# atmega2560test.net
KiCad netlist of a schematic drawn in EAGLE
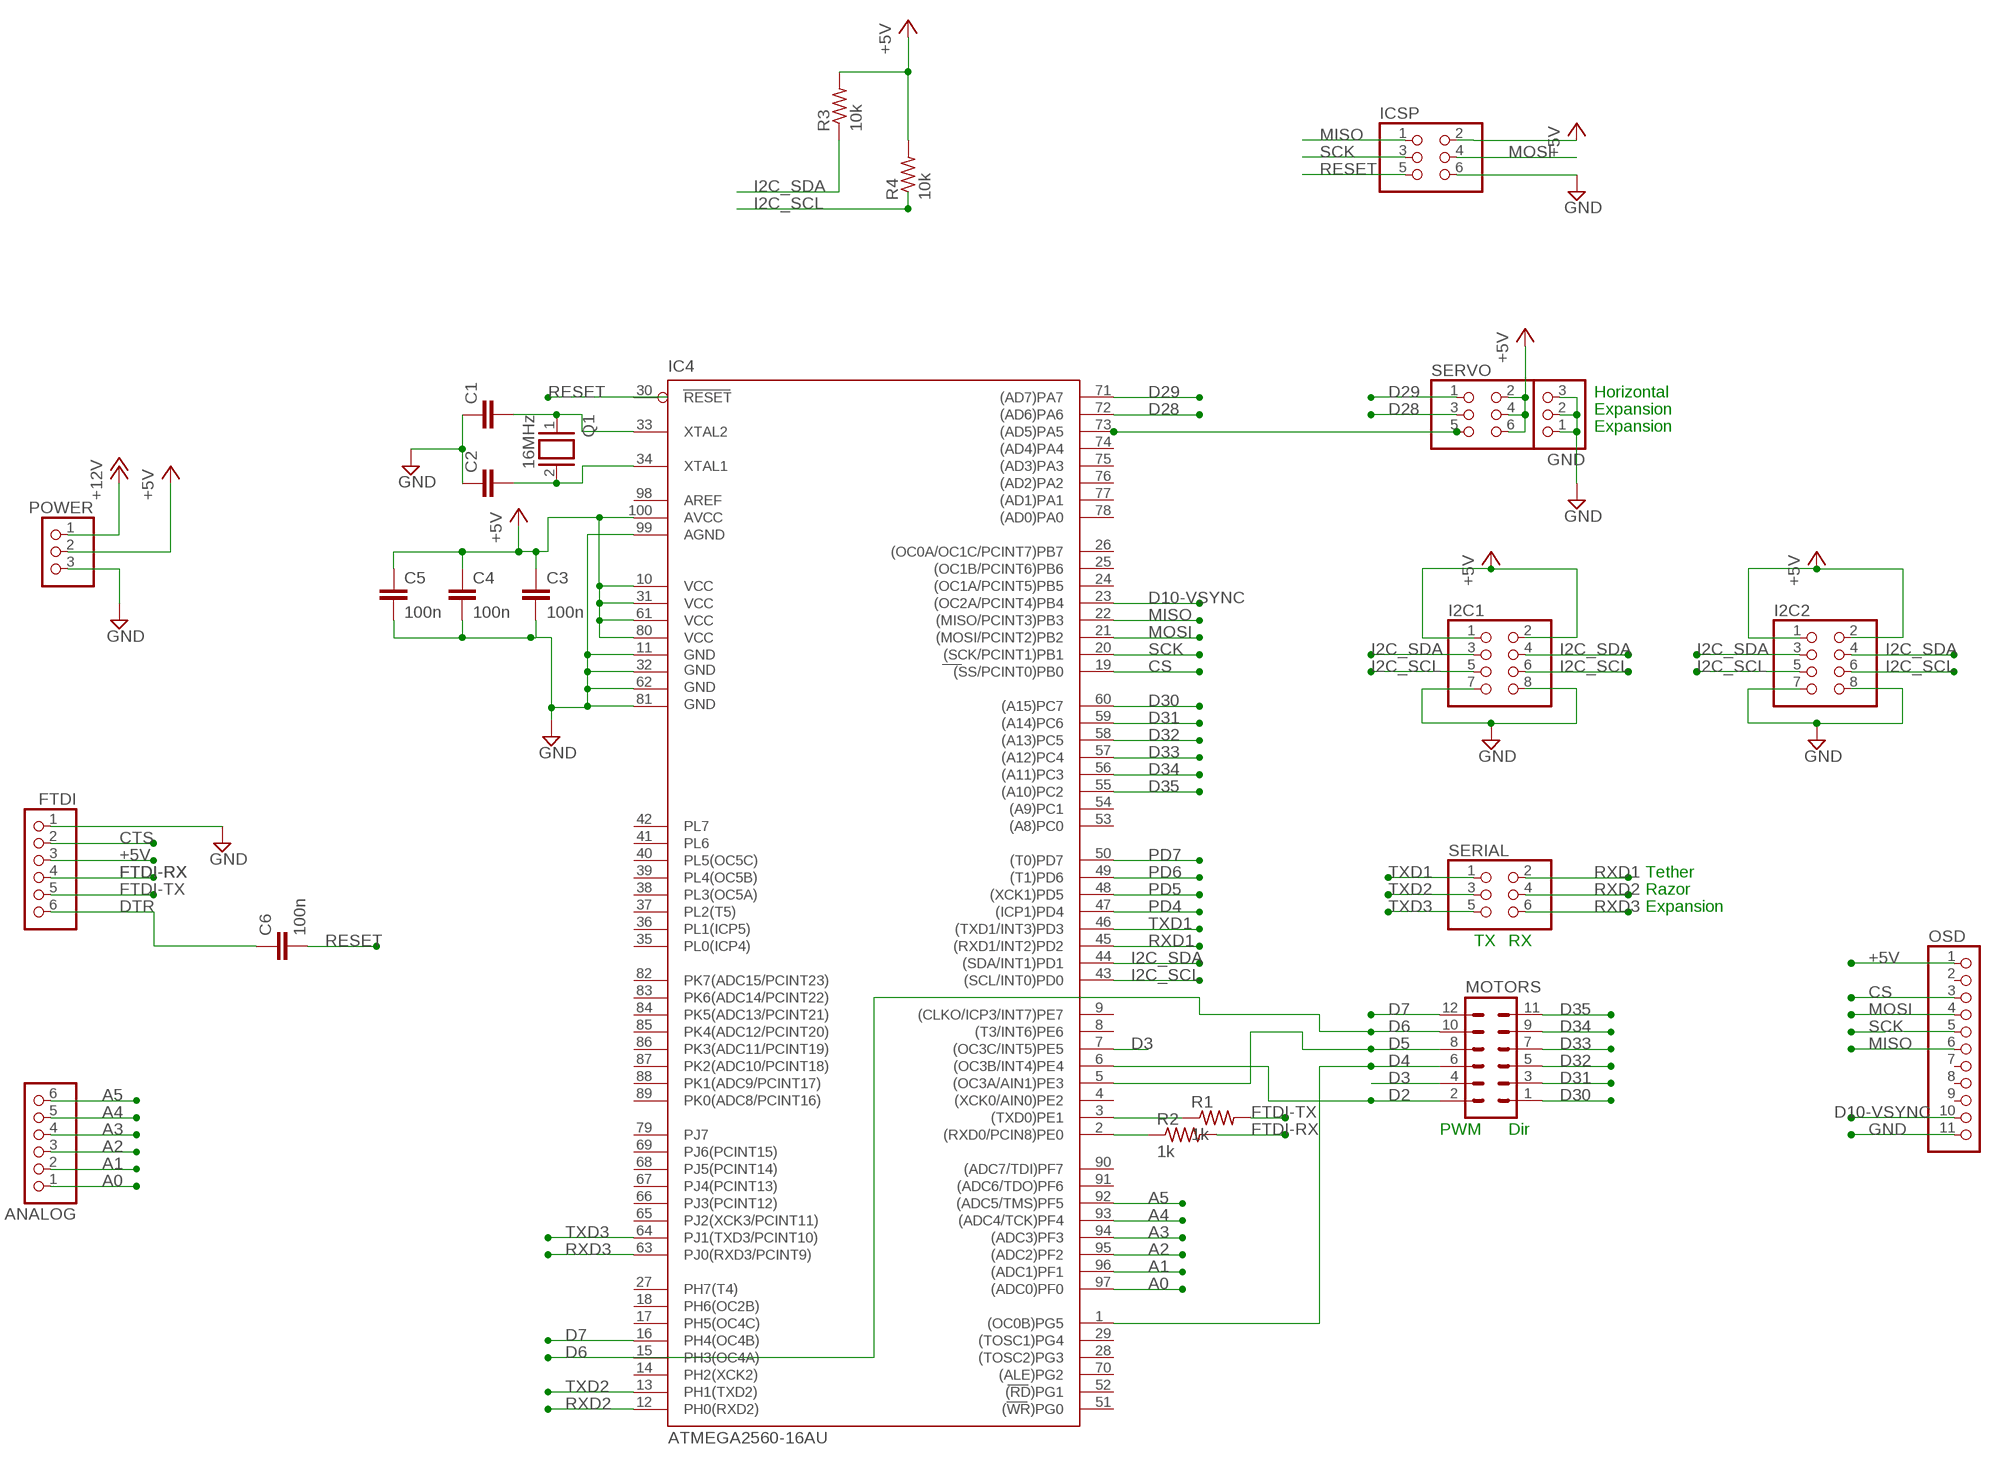
[diagram p0: schematic, sheet 1]

(export (version "E")
  (design (tool "Eeschema 10.0.6"))
  (components
    (comp (ref "ANALOG")
      (value "PINHD-1X6")
      (footprint "eagle-import:1X06")
      (libsource (lib "eagle-import") (part "PINHD-1X6"))
    )
    (comp (ref "C1")
      (value "C5/3.5")
      (footprint "eagle-import:C5B3.5")
      (libsource (lib "eagle-import") (part "C5/3.5"))
    )
    (comp (ref "C2")
      (value "C5/3.5")
      (footprint "eagle-import:C5B3.5")
      (libsource (lib "eagle-import") (part "C5/3.5"))
    )
    (comp (ref "C3")
      (value "100n")
      (footprint "eagle-import:C5B3.5")
      (libsource (lib "eagle-import") (part "C5/3.5"))
    )
    (comp (ref "C4")
      (value "100n")
      (footprint "eagle-import:C5B3.5")
      (libsource (lib "eagle-import") (part "C5/3.5"))
    )
    (comp (ref "C5")
      (value "100n")
      (footprint "eagle-import:C5B3.5")
      (libsource (lib "eagle-import") (part "C5/3.5"))
    )
    (comp (ref "C6")
      (value "100n")
      (footprint "eagle-import:C050-030X075")
      (libsource (lib "eagle-import") (part "C-EU050-030X075"))
    )
    (comp (ref "FTDI")
      (value "PINHD-1X6")
      (footprint "eagle-import:1X06")
      (libsource (lib "eagle-import") (part "PINHD-1X6"))
    )
    (comp (ref "GND")
      (value "PINHD-1X3")
      (footprint "eagle-import:1X03")
      (libsource (lib "eagle-import") (part "PINHD-1X3"))
    )
    (comp (ref "I2C1")
      (value "PINHD-2X4")
      (footprint "eagle-import:2X04")
      (libsource (lib "eagle-import") (part "PINHD-2X4"))
    )
    (comp (ref "I2C2")
      (value "PINHD-2X4")
      (footprint "eagle-import:2X04")
      (libsource (lib "eagle-import") (part "PINHD-2X4"))
    )
    (comp (ref "IC4")
      (value "ATMEGA2560-16AU")
      (footprint "eagle-import:TQFP100")
      (libsource (lib "eagle-import") (part "ATMEGAAU2560-16"))
    )
    (comp (ref "ICSP")
      (value "PINHD-2X3")
      (footprint "eagle-import:2X03")
      (libsource (lib "eagle-import") (part "PINHD-2X3"))
    )
    (comp (ref "MOTORS")
      (value "MA06-2")
      (footprint "eagle-import:MA06-2")
      (libsource (lib "eagle-import") (part "MA06-2"))
    )
    (comp (ref "OSD")
      (value "PINHD-1X11")
      (footprint "eagle-import:1X11")
      (libsource (lib "eagle-import") (part "PINHD-1X11"))
    )
    (comp (ref "POWER")
      (value "PINHD-1X3")
      (footprint "eagle-import:1X03")
      (libsource (lib "eagle-import") (part "PINHD-1X3"))
    )
    (comp (ref "Q1")
      (value "16MHz")
      (footprint "eagle-import:QS")
      (libsource (lib "eagle-import") (part "XTAL/S"))
    )
    (comp (ref "R1")
      (value "1k")
      (footprint "eagle-import:0207_7")
      (libsource (lib "eagle-import") (part "R-US_0207/7"))
    )
    (comp (ref "R2")
      (value "1k")
      (footprint "eagle-import:0207_7")
      (libsource (lib "eagle-import") (part "R-US_0207/7"))
    )
    (comp (ref "R3")
      (value "10k")
      (footprint "eagle-import:0207_7")
      (libsource (lib "eagle-import") (part "R-US_0207/7"))
    )
    (comp (ref "R4")
      (value "10k")
      (footprint "eagle-import:0207_7")
      (libsource (lib "eagle-import") (part "R-US_0207/7"))
    )
    (comp (ref "SERIAL")
      (value "PINHD-2X3")
      (footprint "eagle-import:2X03")
      (libsource (lib "eagle-import") (part "PINHD-2X3"))
    )
    (comp (ref "SERVO")
      (value "PINHD-2X3")
      (footprint "eagle-import:2X03")
      (libsource (lib "eagle-import") (part "PINHD-2X3"))
    )
  )
  (nets
    (net (code "1") (name "+5V") (class "Default")
      (node (ref "C3") (pin "1") (pinfunction "1_1") (pintype "passive"))
      (node (ref "C4") (pin "1") (pinfunction "1_1") (pintype "passive"))
      (node (ref "C5") (pin "1") (pinfunction "1_1") (pintype "passive"))
      (node (ref "FTDI") (pin "3") (pinfunction "3_3") (pintype "passive"))
      (node (ref "I2C1") (pin "1") (pinfunction "1_1") (pintype "passive"))
      (node (ref "I2C1") (pin "2") (pinfunction "2_2") (pintype "passive"))
      (node (ref "I2C2") (pin "1") (pinfunction "1_1") (pintype "passive"))
      (node (ref "I2C2") (pin "2") (pinfunction "2_2") (pintype "passive"))
      (node (ref "IC4") (pin "10") (pinfunction "VCC_10") (pintype "power_in"))
      (node (ref "IC4") (pin "100") (pinfunction "AVCC_100") (pintype "power_in"))
      (node (ref "IC4") (pin "31") (pinfunction "VCC1_31") (pintype "power_in"))
      (node (ref "IC4") (pin "61") (pinfunction "VCC2_61") (pintype "power_in"))
      (node (ref "IC4") (pin "80") (pinfunction "VCC3_80") (pintype "power_in"))
      (node (ref "ICSP") (pin "2") (pinfunction "2_2") (pintype "passive"))
      (node (ref "OSD") (pin "1") (pinfunction "1_1") (pintype "passive"))
      (node (ref "POWER") (pin "2") (pinfunction "2_2") (pintype "passive"))
      (node (ref "R3") (pin "2") (pinfunction "2_2") (pintype "passive"))
      (node (ref "R4") (pin "2") (pinfunction "2_2") (pintype "passive"))
      (node (ref "SERVO") (pin "2") (pinfunction "2_2") (pintype "passive"))
      (node (ref "SERVO") (pin "4") (pinfunction "4_4") (pintype "passive"))
      (node (ref "SERVO") (pin "6") (pinfunction "6_6") (pintype "passive"))
    )
    (net (code "2") (name "+12V") (class "Default")
      (node (ref "POWER") (pin "1") (pinfunction "1_1") (pintype "passive"))
    )
    (net (code "3") (name "/A0") (class "Default")
      (node (ref "ANALOG") (pin "1") (pinfunction "1_1") (pintype "passive"))
      (node (ref "IC4") (pin "97") (pinfunction "(ADC0)PF0_97") (pintype "bidirectional"))
    )
    (net (code "4") (name "/A1") (class "Default")
      (node (ref "ANALOG") (pin "2") (pinfunction "2_2") (pintype "passive"))
      (node (ref "IC4") (pin "96") (pinfunction "(ADC1)PF1_96") (pintype "bidirectional"))
    )
    (net (code "5") (name "/A2") (class "Default")
      (node (ref "ANALOG") (pin "3") (pinfunction "3_3") (pintype "passive"))
      (node (ref "IC4") (pin "95") (pinfunction "(ADC2)PF2_95") (pintype "bidirectional"))
    )
    (net (code "6") (name "/A3") (class "Default")
      (node (ref "ANALOG") (pin "4") (pinfunction "4_4") (pintype "passive"))
      (node (ref "IC4") (pin "94") (pinfunction "(ADC3)PF3_94") (pintype "bidirectional"))
    )
    (net (code "7") (name "/A4") (class "Default")
      (node (ref "ANALOG") (pin "5") (pinfunction "5_5") (pintype "passive"))
      (node (ref "IC4") (pin "93") (pinfunction "(ADC4/TCK)PF4_93") (pintype "bidirectional"))
    )
    (net (code "8") (name "/A5") (class "Default")
      (node (ref "ANALOG") (pin "6") (pinfunction "6_6") (pintype "passive"))
      (node (ref "IC4") (pin "92") (pinfunction "(ADC5/TMS)PF5_92") (pintype "bidirectional"))
    )
    (net (code "9") (name "/CS") (class "Default")
      (node (ref "IC4") (pin "19") (pinfunction "(SS/PCINT0)PB0_19") (pintype "bidirectional"))
      (node (ref "OSD") (pin "3") (pinfunction "3_3") (pintype "passive"))
    )
    (net (code "10") (name "/CTS") (class "Default")
      (node (ref "FTDI") (pin "2") (pinfunction "2_2") (pintype "passive"))
    )
    (net (code "11") (name "/D2") (class "Default")
      (node (ref "IC4") (pin "6") (pinfunction "(OC3B/INT4)PE4_6") (pintype "bidirectional"))
      (node (ref "MOTORS") (pin "2") (pinfunction "2_2") (pintype "passive"))
    )
    (net (code "12") (name "/D3") (class "Default")
      (node (ref "IC4") (pin "7") (pinfunction "(OC3C/INT5)PE5_7") (pintype "bidirectional"))
      (node (ref "MOTORS") (pin "4") (pinfunction "4_4") (pintype "passive"))
    )
    (net (code "13") (name "/D4") (class "Default")
      (node (ref "IC4") (pin "1") (pinfunction "(OC0B)PG5_1") (pintype "bidirectional"))
      (node (ref "MOTORS") (pin "6") (pinfunction "6_6") (pintype "passive"))
    )
    (net (code "14") (name "/D5") (class "Default")
      (node (ref "IC4") (pin "5") (pinfunction "(OC3A/AIN1)PE3_5") (pintype "bidirectional"))
      (node (ref "MOTORS") (pin "8") (pinfunction "8_8") (pintype "passive"))
    )
    (net (code "15") (name "/D6") (class "Default")
      (node (ref "IC4") (pin "15") (pinfunction "PH3(OC4A)_15") (pintype "bidirectional"))
      (node (ref "MOTORS") (pin "10") (pinfunction "10_10") (pintype "passive"))
    )
    (net (code "16") (name "/D7") (class "Default")
      (node (ref "IC4") (pin "16") (pinfunction "PH4(OC4B)_16") (pintype "bidirectional"))
      (node (ref "MOTORS") (pin "12") (pinfunction "12_12") (pintype "passive"))
    )
    (net (code "17") (name "/D10-VSYNC") (class "Default")
      (node (ref "IC4") (pin "23") (pinfunction "(OC2A/PCINT4)PB4_23") (pintype "bidirectional"))
      (node (ref "OSD") (pin "10") (pinfunction "10_10") (pintype "passive"))
    )
    (net (code "18") (name "/D28") (class "Default")
      (node (ref "IC4") (pin "72") (pinfunction "(AD6)PA6_72") (pintype "bidirectional"))
      (node (ref "SERVO") (pin "3") (pinfunction "3_3") (pintype "passive"))
    )
    (net (code "19") (name "/D29") (class "Default")
      (node (ref "IC4") (pin "71") (pinfunction "(AD7)PA7_71") (pintype "bidirectional"))
      (node (ref "SERVO") (pin "1") (pinfunction "1_1") (pintype "passive"))
    )
    (net (code "20") (name "/D30") (class "Default")
      (node (ref "IC4") (pin "60") (pinfunction "(A15)PC7_60") (pintype "bidirectional"))
      (node (ref "MOTORS") (pin "1") (pinfunction "1_1") (pintype "passive"))
    )
    (net (code "21") (name "/D31") (class "Default")
      (node (ref "IC4") (pin "59") (pinfunction "(A14)PC6_59") (pintype "bidirectional"))
      (node (ref "MOTORS") (pin "3") (pinfunction "3_3") (pintype "passive"))
    )
    (net (code "22") (name "/D32") (class "Default")
      (node (ref "IC4") (pin "58") (pinfunction "(A13)PC5_58") (pintype "bidirectional"))
      (node (ref "MOTORS") (pin "5") (pinfunction "5_5") (pintype "passive"))
    )
    (net (code "23") (name "/D33") (class "Default")
      (node (ref "IC4") (pin "57") (pinfunction "(A12)PC4_57") (pintype "bidirectional"))
      (node (ref "MOTORS") (pin "7") (pinfunction "7_7") (pintype "passive"))
    )
    (net (code "24") (name "/D34") (class "Default")
      (node (ref "IC4") (pin "56") (pinfunction "(A11)PC3_56") (pintype "bidirectional"))
      (node (ref "MOTORS") (pin "9") (pinfunction "9_9") (pintype "passive"))
    )
    (net (code "25") (name "/D35") (class "Default")
      (node (ref "IC4") (pin "55") (pinfunction "(A10)PC2_55") (pintype "bidirectional"))
      (node (ref "MOTORS") (pin "11") (pinfunction "11_11") (pintype "passive"))
    )
    (net (code "26") (name "/DTR") (class "Default")
      (node (ref "C6") (pin "1") (pinfunction "1_1") (pintype "passive"))
      (node (ref "FTDI") (pin "6") (pinfunction "6_6") (pintype "passive"))
    )
    (net (code "27") (name "/FTDI-RX") (class "Default")
      (node (ref "FTDI") (pin "4") (pinfunction "4_4") (pintype "passive"))
      (node (ref "R2") (pin "2") (pinfunction "2_2") (pintype "passive"))
    )
    (net (code "28") (name "/FTDI-TX") (class "Default")
      (node (ref "FTDI") (pin "5") (pinfunction "5_5") (pintype "passive"))
      (node (ref "R1") (pin "2") (pinfunction "2_2") (pintype "passive"))
    )
    (net (code "29") (name "/I2C_SCL") (class "Default")
      (node (ref "I2C1") (pin "5") (pinfunction "5_5") (pintype "passive"))
      (node (ref "I2C1") (pin "6") (pinfunction "6_6") (pintype "passive"))
      (node (ref "I2C2") (pin "5") (pinfunction "5_5") (pintype "passive"))
      (node (ref "I2C2") (pin "6") (pinfunction "6_6") (pintype "passive"))
      (node (ref "IC4") (pin "43") (pinfunction "(SCL/INT0)PD0_43") (pintype "bidirectional"))
      (node (ref "R4") (pin "1") (pinfunction "1_1") (pintype "passive"))
    )
    (net (code "30") (name "/I2C_SDA") (class "Default")
      (node (ref "I2C1") (pin "3") (pinfunction "3_3") (pintype "passive"))
      (node (ref "I2C1") (pin "4") (pinfunction "4_4") (pintype "passive"))
      (node (ref "I2C2") (pin "3") (pinfunction "3_3") (pintype "passive"))
      (node (ref "I2C2") (pin "4") (pinfunction "4_4") (pintype "passive"))
      (node (ref "IC4") (pin "44") (pinfunction "(SDA/INT1)PD1_44") (pintype "bidirectional"))
      (node (ref "R3") (pin "1") (pinfunction "1_1") (pintype "passive"))
    )
    (net (code "31") (name "/MISO") (class "Default")
      (node (ref "IC4") (pin "22") (pinfunction "(MISO/PCINT3)PB3_22") (pintype "bidirectional"))
      (node (ref "ICSP") (pin "1") (pinfunction "1_1") (pintype "passive"))
      (node (ref "OSD") (pin "6") (pinfunction "6_6") (pintype "passive"))
    )
    (net (code "32") (name "/MOSI") (class "Default")
      (node (ref "IC4") (pin "21") (pinfunction "(MOSI/PCINT2)PB2_21") (pintype "bidirectional"))
      (node (ref "ICSP") (pin "4") (pinfunction "4_4") (pintype "passive"))
      (node (ref "OSD") (pin "4") (pinfunction "4_4") (pintype "passive"))
    )
    (net (code "33") (name "/PD4") (class "Default")
      (node (ref "IC4") (pin "47") (pinfunction "(ICP1)PD4_47") (pintype "bidirectional"))
    )
    (net (code "34") (name "/PD5") (class "Default")
      (node (ref "IC4") (pin "48") (pinfunction "(XCK1)PD5_48") (pintype "bidirectional"))
    )
    (net (code "35") (name "/PD6") (class "Default")
      (node (ref "IC4") (pin "49") (pinfunction "(T1)PD6_49") (pintype "bidirectional"))
    )
    (net (code "36") (name "/PD7") (class "Default")
      (node (ref "IC4") (pin "50") (pinfunction "(T0)PD7_50") (pintype "bidirectional"))
    )
    (net (code "37") (name "/RESET") (class "Default")
      (node (ref "C6") (pin "2") (pinfunction "2_2") (pintype "passive"))
      (node (ref "ICSP") (pin "5") (pinfunction "5_5") (pintype "passive"))
    )
    (net (code "38") (name "/RXD1") (class "Default")
      (node (ref "IC4") (pin "45") (pinfunction "(RXD1/INT2)PD2_45") (pintype "bidirectional"))
      (node (ref "SERIAL") (pin "2") (pinfunction "2_2") (pintype "passive"))
    )
    (net (code "39") (name "/RXD2") (class "Default")
      (node (ref "IC4") (pin "12") (pinfunction "PH0(RXD2)_12") (pintype "bidirectional"))
      (node (ref "SERIAL") (pin "4") (pinfunction "4_4") (pintype "passive"))
    )
    (net (code "40") (name "/RXD3") (class "Default")
      (node (ref "IC4") (pin "63") (pinfunction "PJ0(RXD3/PCINT9)_63") (pintype "bidirectional"))
      (node (ref "SERIAL") (pin "6") (pinfunction "6_6") (pintype "passive"))
    )
    (net (code "41") (name "/SCK") (class "Default")
      (node (ref "IC4") (pin "20") (pinfunction "(SCK/PCINT1)PB1_20") (pintype "bidirectional"))
      (node (ref "ICSP") (pin "3") (pinfunction "3_3") (pintype "passive"))
      (node (ref "OSD") (pin "5") (pinfunction "5_5") (pintype "passive"))
    )
    (net (code "42") (name "/TXD1") (class "Default")
      (node (ref "IC4") (pin "46") (pinfunction "(TXD1/INT3)PD3_46") (pintype "bidirectional"))
      (node (ref "SERIAL") (pin "1") (pinfunction "1_1") (pintype "passive"))
    )
    (net (code "43") (name "/TXD2") (class "Default")
      (node (ref "IC4") (pin "13") (pinfunction "PH1(TXD2)_13") (pintype "bidirectional"))
      (node (ref "SERIAL") (pin "3") (pinfunction "3_3") (pintype "passive"))
    )
    (net (code "44") (name "/TXD3") (class "Default")
      (node (ref "IC4") (pin "64") (pinfunction "PJ1(TXD3/PCINT10)_64") (pintype "bidirectional"))
      (node (ref "SERIAL") (pin "5") (pinfunction "5_5") (pintype "passive"))
    )
    (net (code "45") (name "GND") (class "Default")
      (node (ref "C1") (pin "1") (pinfunction "1_1") (pintype "passive"))
      (node (ref "C2") (pin "1") (pinfunction "1_1") (pintype "passive"))
      (node (ref "C3") (pin "2") (pinfunction "2_2") (pintype "passive"))
      (node (ref "C4") (pin "2") (pinfunction "2_2") (pintype "passive"))
      (node (ref "C5") (pin "2") (pinfunction "2_2") (pintype "passive"))
      (node (ref "FTDI") (pin "1") (pinfunction "1_1") (pintype "passive"))
      (node (ref "GND") (pin "1") (pinfunction "1_1") (pintype "passive"))
      (node (ref "GND") (pin "2") (pinfunction "2_2") (pintype "passive"))
      (node (ref "GND") (pin "3") (pinfunction "3_3") (pintype "passive"))
      (node (ref "I2C1") (pin "7") (pinfunction "7_7") (pintype "passive"))
      (node (ref "I2C1") (pin "8") (pinfunction "8_8") (pintype "passive"))
      (node (ref "I2C2") (pin "7") (pinfunction "7_7") (pintype "passive"))
      (node (ref "I2C2") (pin "8") (pinfunction "8_8") (pintype "passive"))
      (node (ref "IC4") (pin "11") (pinfunction "GND_11") (pintype "power_in"))
      (node (ref "IC4") (pin "32") (pinfunction "GND1_32") (pintype "power_in"))
      (node (ref "IC4") (pin "62") (pinfunction "GND2_62") (pintype "power_in"))
      (node (ref "IC4") (pin "81") (pinfunction "GND3_81") (pintype "power_in"))
      (node (ref "IC4") (pin "99") (pinfunction "AGND_99") (pintype "power_in"))
      (node (ref "ICSP") (pin "6") (pinfunction "6_6") (pintype "passive"))
      (node (ref "OSD") (pin "11") (pinfunction "11_11") (pintype "passive"))
      (node (ref "POWER") (pin "3") (pinfunction "3_3") (pintype "passive"))
    )
    (net (code "46") (name "Net-(IC4-(AD5)PA5)") (class "Default")
      (node (ref "IC4") (pin "73") (pinfunction "(AD5)PA5_73") (pintype "bidirectional"))
      (node (ref "SERVO") (pin "5") (pinfunction "5_5") (pintype "passive"))
    )
    (net (code "47") (name "Net-(IC4-(RXD0{slash}PCIN8)PE0)") (class "Default")
      (node (ref "IC4") (pin "2") (pinfunction "(RXD0/PCIN8)PE0_2") (pintype "bidirectional"))
      (node (ref "R2") (pin "1") (pinfunction "1_1") (pintype "passive"))
    )
    (net (code "48") (name "Net-(IC4-(TXD0)PE1)") (class "Default")
      (node (ref "IC4") (pin "3") (pinfunction "(TXD0)PE1_3") (pintype "bidirectional"))
      (node (ref "R1") (pin "1") (pinfunction "1_1") (pintype "passive"))
    )
    (net (code "49") (name "Net-(IC4-XTAL1)") (class "Default")
      (node (ref "C2") (pin "2") (pinfunction "2_2") (pintype "passive"))
      (node (ref "IC4") (pin "34") (pinfunction "XTAL1_34") (pintype "input"))
      (node (ref "Q1") (pin "2") (pinfunction "2_2") (pintype "passive"))
    )
    (net (code "50") (name "Net-(IC4-XTAL2)") (class "Default")
      (node (ref "C1") (pin "2") (pinfunction "2_2") (pintype "passive"))
      (node (ref "IC4") (pin "33") (pinfunction "XTAL2_33") (pintype "output"))
      (node (ref "Q1") (pin "1") (pinfunction "1_1") (pintype "passive"))
    )
    (net (code "51") (name "unconnected-(IC4-(A8)PC0-Pad53)") (class "Default")
      (node (ref "IC4") (pin "53") (pinfunction "(A8)PC0_53") (pintype "bidirectional"))
    )
    (net (code "52") (name "unconnected-(IC4-(A9)PC1-Pad54)") (class "Default")
      (node (ref "IC4") (pin "54") (pinfunction "(A9)PC1_54") (pintype "bidirectional"))
    )
    (net (code "53") (name "unconnected-(IC4-(AD0)PA0-Pad78)") (class "Default")
      (node (ref "IC4") (pin "78") (pinfunction "(AD0)PA0_78") (pintype "bidirectional"))
    )
    (net (code "54") (name "unconnected-(IC4-(AD1)PA1-Pad77)") (class "Default")
      (node (ref "IC4") (pin "77") (pinfunction "(AD1)PA1_77") (pintype "bidirectional"))
    )
    (net (code "55") (name "unconnected-(IC4-(AD2)PA2-Pad76)") (class "Default")
      (node (ref "IC4") (pin "76") (pinfunction "(AD2)PA2_76") (pintype "bidirectional"))
    )
    (net (code "56") (name "unconnected-(IC4-(AD3)PA3-Pad75)") (class "Default")
      (node (ref "IC4") (pin "75") (pinfunction "(AD3)PA3_75") (pintype "bidirectional"))
    )
    (net (code "57") (name "unconnected-(IC4-(AD4)PA4-Pad74)") (class "Default")
      (node (ref "IC4") (pin "74") (pinfunction "(AD4)PA4_74") (pintype "bidirectional"))
    )
    (net (code "58") (name "unconnected-(IC4-(ADC6{slash}TDO)PF6-Pad91)") (class "Default")
      (node (ref "IC4") (pin "91") (pinfunction "(ADC6/TDO)PF6_91") (pintype "bidirectional"))
    )
    (net (code "59") (name "unconnected-(IC4-(ADC7{slash}TDI)PF7-Pad90)") (class "Default")
      (node (ref "IC4") (pin "90") (pinfunction "(ADC7/TDI)PF7_90") (pintype "bidirectional"))
    )
    (net (code "60") (name "unconnected-(IC4-(ALE)PG2-Pad70)") (class "Default")
      (node (ref "IC4") (pin "70") (pinfunction "(ALE)PG2_70") (pintype "bidirectional"))
    )
    (net (code "61") (name "unconnected-(IC4-(CLKO{slash}ICP3{slash}INT7)PE7-Pad9)") (class "Default")
      (node (ref "IC4") (pin "9") (pinfunction "(CLKO/ICP3/INT7)PE7_9") (pintype "bidirectional"))
    )
    (net (code "62") (name "unconnected-(IC4-(OC0A{slash}OC1C{slash}PCINT7)PB7-Pad26)") (class "Default")
      (node (ref "IC4") (pin "26") (pinfunction "(OC0A/OC1C/PCINT7)PB7_26") (pintype "bidirectional"))
    )
    (net (code "63") (name "unconnected-(IC4-(OC1A{slash}PCINT5)PB5-Pad24)") (class "Default")
      (node (ref "IC4") (pin "24") (pinfunction "(OC1A/PCINT5)PB5_24") (pintype "bidirectional"))
    )
    (net (code "64") (name "unconnected-(IC4-(OC1B{slash}PCINT6)PB6-Pad25)") (class "Default")
      (node (ref "IC4") (pin "25") (pinfunction "(OC1B/PCINT6)PB6_25") (pintype "bidirectional"))
    )
    (net (code "65") (name "unconnected-(IC4-(RD)PG1-Pad52)") (class "Default")
      (node (ref "IC4") (pin "52") (pinfunction "(RD)PG1_52") (pintype "bidirectional"))
    )
    (net (code "66") (name "unconnected-(IC4-(T3{slash}INT6)PE6-Pad8)") (class "Default")
      (node (ref "IC4") (pin "8") (pinfunction "(T3/INT6)PE6_8") (pintype "bidirectional"))
    )
    (net (code "67") (name "unconnected-(IC4-(TOSC1)PG4-Pad29)") (class "Default")
      (node (ref "IC4") (pin "29") (pinfunction "(TOSC1)PG4_29") (pintype "bidirectional"))
    )
    (net (code "68") (name "unconnected-(IC4-(TOSC2)PG3-Pad28)") (class "Default")
      (node (ref "IC4") (pin "28") (pinfunction "(TOSC2)PG3_28") (pintype "bidirectional"))
    )
    (net (code "69") (name "unconnected-(IC4-(WR)PG0-Pad51)") (class "Default")
      (node (ref "IC4") (pin "51") (pinfunction "(WR)PG0_51") (pintype "bidirectional"))
    )
    (net (code "70") (name "unconnected-(IC4-(XCK0{slash}AIN0)PE2-Pad4)") (class "Default")
      (node (ref "IC4") (pin "4") (pinfunction "(XCK0/AIN0)PE2_4") (pintype "bidirectional"))
    )
    (net (code "71") (name "unconnected-(IC4-AREF-Pad98)") (class "Default")
      (node (ref "IC4") (pin "98") (pinfunction "AREF_98") (pintype "bidirectional"))
    )
    (net (code "72") (name "unconnected-(IC4-PH2(XCK2)-Pad14)") (class "Default")
      (node (ref "IC4") (pin "14") (pinfunction "PH2(XCK2)_14") (pintype "bidirectional"))
    )
    (net (code "73") (name "unconnected-(IC4-PH5(OC4C)-Pad17)") (class "Default")
      (node (ref "IC4") (pin "17") (pinfunction "PH5(OC4C)_17") (pintype "bidirectional"))
    )
    (net (code "74") (name "unconnected-(IC4-PH6(OC2B)-Pad18)") (class "Default")
      (node (ref "IC4") (pin "18") (pinfunction "PH6(OC2B)_18") (pintype "bidirectional"))
    )
    (net (code "75") (name "unconnected-(IC4-PH7(T4)-Pad27)") (class "Default")
      (node (ref "IC4") (pin "27") (pinfunction "PH7(T4)_27") (pintype "bidirectional"))
    )
    (net (code "76") (name "unconnected-(IC4-PJ2(XCK3{slash}PCINT11)-Pad65)") (class "Default")
      (node (ref "IC4") (pin "65") (pinfunction "PJ2(XCK3/PCINT11)_65") (pintype "bidirectional"))
    )
    (net (code "77") (name "unconnected-(IC4-PJ3(PCINT12)-Pad66)") (class "Default")
      (node (ref "IC4") (pin "66") (pinfunction "PJ3(PCINT12)_66") (pintype "bidirectional"))
    )
    (net (code "78") (name "unconnected-(IC4-PJ4(PCINT13)-Pad67)") (class "Default")
      (node (ref "IC4") (pin "67") (pinfunction "PJ4(PCINT13)_67") (pintype "bidirectional"))
    )
    (net (code "79") (name "unconnected-(IC4-PJ5(PCINT14)-Pad68)") (class "Default")
      (node (ref "IC4") (pin "68") (pinfunction "PJ5(PCINT14)_68") (pintype "bidirectional"))
    )
    (net (code "80") (name "unconnected-(IC4-PJ6(PCINT15)-Pad69)") (class "Default")
      (node (ref "IC4") (pin "69") (pinfunction "PJ6(PCINT15)_69") (pintype "bidirectional"))
    )
    (net (code "81") (name "unconnected-(IC4-PJ7-Pad79)") (class "Default")
      (node (ref "IC4") (pin "79") (pinfunction "PJ7_79") (pintype "bidirectional"))
    )
    (net (code "82") (name "unconnected-(IC4-PK0(ADC8{slash}PCINT16)-Pad89)") (class "Default")
      (node (ref "IC4") (pin "89") (pinfunction "PK0(ADC8/PCINT16)_89") (pintype "bidirectional"))
    )
    (net (code "83") (name "unconnected-(IC4-PK1(ADC9{slash}PCINT17)-Pad88)") (class "Default")
      (node (ref "IC4") (pin "88") (pinfunction "PK1(ADC9/PCINT17)_88") (pintype "bidirectional"))
    )
    (net (code "84") (name "unconnected-(IC4-PK2(ADC10{slash}PCINT18)-Pad87)") (class "Default")
      (node (ref "IC4") (pin "87") (pinfunction "PK2(ADC10/PCINT18)_87") (pintype "bidirectional"))
    )
    (net (code "85") (name "unconnected-(IC4-PK3(ADC11{slash}PCINT19)-Pad86)") (class "Default")
      (node (ref "IC4") (pin "86") (pinfunction "PK3(ADC11/PCINT19)_86") (pintype "bidirectional"))
    )
    (net (code "86") (name "unconnected-(IC4-PK4(ADC12{slash}PCINT20)-Pad85)") (class "Default")
      (node (ref "IC4") (pin "85") (pinfunction "PK4(ADC12/PCINT20)_85") (pintype "bidirectional"))
    )
    (net (code "87") (name "unconnected-(IC4-PK5(ADC13{slash}PCINT21)-Pad84)") (class "Default")
      (node (ref "IC4") (pin "84") (pinfunction "PK5(ADC13/PCINT21)_84") (pintype "bidirectional"))
    )
    (net (code "88") (name "unconnected-(IC4-PK6(ADC14{slash}PCINT22)-Pad83)") (class "Default")
      (node (ref "IC4") (pin "83") (pinfunction "PK6(ADC14/PCINT22)_83") (pintype "bidirectional"))
    )
    (net (code "89") (name "unconnected-(IC4-PK7(ADC15{slash}PCINT23)-Pad82)") (class "Default")
      (node (ref "IC4") (pin "82") (pinfunction "PK7(ADC15/PCINT23)_82") (pintype "bidirectional"))
    )
    (net (code "90") (name "unconnected-(IC4-PL0(ICP4)-Pad35)") (class "Default")
      (node (ref "IC4") (pin "35") (pinfunction "PL0(ICP4)_35") (pintype "bidirectional"))
    )
    (net (code "91") (name "unconnected-(IC4-PL1(ICP5)-Pad36)") (class "Default")
      (node (ref "IC4") (pin "36") (pinfunction "PL1(ICP5)_36") (pintype "bidirectional"))
    )
    (net (code "92") (name "unconnected-(IC4-PL2(T5)-Pad37)") (class "Default")
      (node (ref "IC4") (pin "37") (pinfunction "PL2(T5)_37") (pintype "bidirectional"))
    )
    (net (code "93") (name "unconnected-(IC4-PL3(OC5A)-Pad38)") (class "Default")
      (node (ref "IC4") (pin "38") (pinfunction "PL3(OC5A)_38") (pintype "bidirectional"))
    )
    (net (code "94") (name "unconnected-(IC4-PL4(OC5B)-Pad39)") (class "Default")
      (node (ref "IC4") (pin "39") (pinfunction "PL4(OC5B)_39") (pintype "bidirectional"))
    )
    (net (code "95") (name "unconnected-(IC4-PL5(OC5C)-Pad40)") (class "Default")
      (node (ref "IC4") (pin "40") (pinfunction "PL5(OC5C)_40") (pintype "bidirectional"))
    )
    (net (code "96") (name "unconnected-(IC4-PL6-Pad41)") (class "Default")
      (node (ref "IC4") (pin "41") (pinfunction "PL6_41") (pintype "bidirectional"))
    )
    (net (code "97") (name "unconnected-(IC4-PL7-Pad42)") (class "Default")
      (node (ref "IC4") (pin "42") (pinfunction "PL7_42") (pintype "bidirectional"))
    )
    (net (code "98") (name "unconnected-(IC4-RESET-Pad30)") (class "Default")
      (node (ref "IC4") (pin "30") (pinfunction "RESET_30") (pintype "input"))
    )
    (net (code "99") (name "unconnected-(OSD-Pad2)") (class "Default")
      (node (ref "OSD") (pin "2") (pinfunction "2_2") (pintype "passive"))
    )
    (net (code "100") (name "unconnected-(OSD-Pad7)") (class "Default")
      (node (ref "OSD") (pin "7") (pinfunction "7_7") (pintype "passive"))
    )
    (net (code "101") (name "unconnected-(OSD-Pad8)") (class "Default")
      (node (ref "OSD") (pin "8") (pinfunction "8_8") (pintype "passive"))
    )
    (net (code "102") (name "unconnected-(OSD-Pad9)") (class "Default")
      (node (ref "OSD") (pin "9") (pinfunction "9_9") (pintype "passive"))
    )
  )
)
